# main.net
KiCad netlist of a schematic drawn in EAGLE
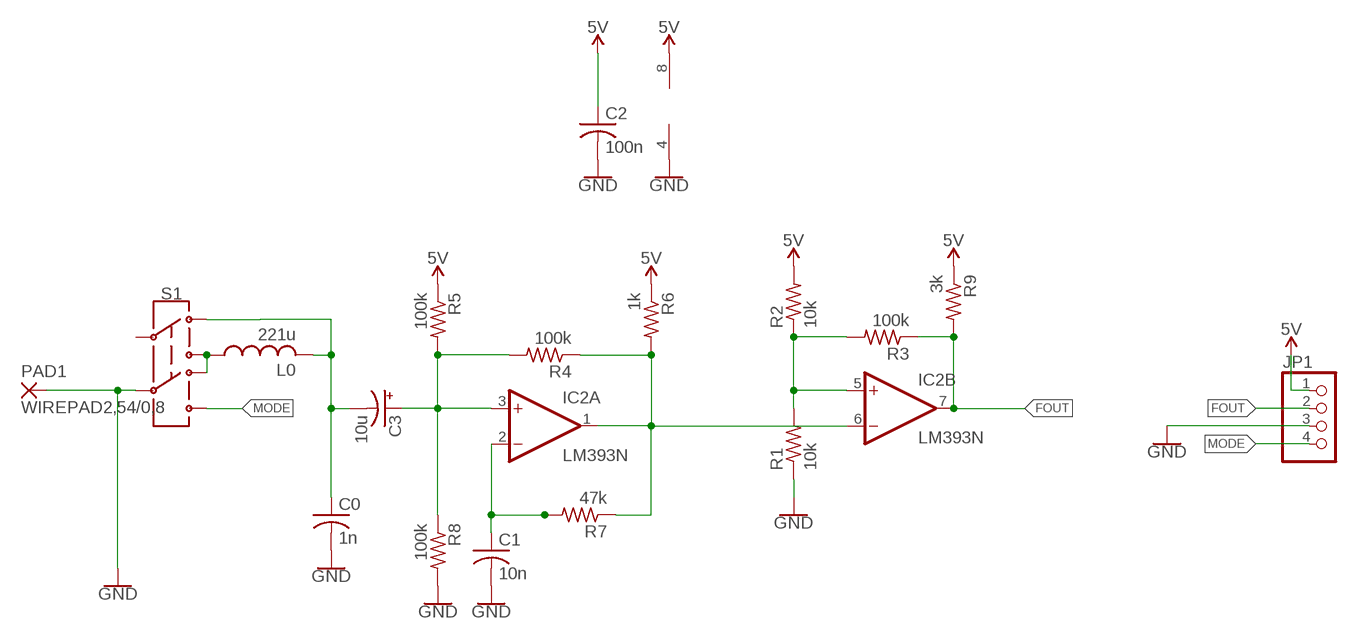
[diagram p0: schematic, sheet 1]

(export (version "E")
  (design (tool "Eeschema 10.0.6"))
  (components
    (comp (ref "C0")
      (value "1n")
      (footprint "eagle-import:C025-025X050")
      (libsource (lib "eagle-import") (part "C-US025-025X050"))
    )
    (comp (ref "C1")
      (value "10n")
      (footprint "eagle-import:C025-025X050")
      (libsource (lib "eagle-import") (part "C-US025-025X050"))
    )
    (comp (ref "C2")
      (value "100n")
      (footprint "eagle-import:C025-025X050")
      (libsource (lib "eagle-import") (part "C-US025-025X050"))
    )
    (comp (ref "C3")
      (value "10u")
      (footprint "eagle-import:E2,5-6")
      (libsource (lib "eagle-import") (part "CPOL-USE2.5-6"))
    )
    (comp (ref "IC2")
      (value "LM393N")
      (footprint "eagle-import:DIL08")
      (libsource (lib "eagle-import") (part "LM393N"))
    )
    (comp (ref "JP1")
      (value "PINHD-1X4")
      (footprint "eagle-import:1X04")
      (libsource (lib "eagle-import") (part "PINHD-1X4"))
    )
    (comp (ref "L0")
      (value "221u")
      (footprint "eagle-import:0204_5")
      (libsource (lib "eagle-import") (part "L-US0204/5"))
    )
    (comp (ref "PAD1")
      (value "WIREPAD2,54/0,8")
      (footprint "eagle-import:2,54_0,8")
      (libsource (lib "eagle-import") (part "WIREPAD2,54/0,8"))
    )
    (comp (ref "R1")
      (value "10k")
      (footprint "eagle-import:0204_7")
      (libsource (lib "eagle-import") (part "R-US_0204/7"))
    )
    (comp (ref "R2")
      (value "10k")
      (footprint "eagle-import:0207_10")
      (libsource (lib "eagle-import") (part "R-US_0207/10"))
    )
    (comp (ref "R3")
      (value "100k")
      (footprint "eagle-import:0207_10")
      (libsource (lib "eagle-import") (part "R-US_0207/10"))
    )
    (comp (ref "R4")
      (value "100k")
      (footprint "eagle-import:0207_10")
      (libsource (lib "eagle-import") (part "R-US_0207/10"))
    )
    (comp (ref "R5")
      (value "100k")
      (footprint "eagle-import:0207_10")
      (libsource (lib "eagle-import") (part "R-US_0207/10"))
    )
    (comp (ref "R6")
      (value "1k")
      (footprint "eagle-import:0207_10")
      (libsource (lib "eagle-import") (part "R-US_0207/10"))
    )
    (comp (ref "R7")
      (value "47k")
      (footprint "eagle-import:0207_10")
      (libsource (lib "eagle-import") (part "R-US_0207/10"))
    )
    (comp (ref "R8")
      (value "100k")
      (footprint "eagle-import:0207_10")
      (libsource (lib "eagle-import") (part "R-US_0207/10"))
    )
    (comp (ref "R9")
      (value "3k")
      (footprint "eagle-import:0207_10")
      (libsource (lib "eagle-import") (part "R-US_0207/10"))
    )
    (comp (ref "S1")
      (value "SWITCH-DPDT-PTH-GPI-152-3013")
      (footprint "eagle-import:SWITCH_DPDT_PTH_GPI-152-3013")
      (libsource (lib "eagle-import") (part "SWITCH-DPDT-PTH-GPI-152-3013"))
    )
  )
  (nets
    (net (code "1") (name "5V") (class "Default")
      (node (ref "C2") (pin "1") (pinfunction "1_1") (pintype "passive"))
      (node (ref "IC2") (pin "8") (pinfunction "V+_8") (pintype "power_in"))
      (node (ref "JP1") (pin "1") (pinfunction "1_1") (pintype "passive"))
      (node (ref "R2") (pin "2") (pinfunction "2_2") (pintype "passive"))
      (node (ref "R5") (pin "1") (pinfunction "1_1") (pintype "passive"))
      (node (ref "R6") (pin "1") (pinfunction "1_1") (pintype "passive"))
      (node (ref "R9") (pin "1") (pinfunction "1_1") (pintype "passive"))
    )
    (net (code "2") (name "FOUT") (class "Default")
      (node (ref "IC2") (pin "7") (pinfunction "OUT_7") (pintype "output"))
      (node (ref "JP1") (pin "2") (pinfunction "2_2") (pintype "passive"))
      (node (ref "R3") (pin "1") (pinfunction "1_1") (pintype "passive"))
      (node (ref "R9") (pin "2") (pinfunction "2_2") (pintype "passive"))
    )
    (net (code "3") (name "GND") (class "Default")
      (node (ref "C0") (pin "2") (pinfunction "2_2") (pintype "passive"))
      (node (ref "C1") (pin "2") (pinfunction "2_2") (pintype "passive"))
      (node (ref "C2") (pin "2") (pinfunction "2_2") (pintype "passive"))
      (node (ref "IC2") (pin "4") (pinfunction "V-_4") (pintype "power_in"))
      (node (ref "JP1") (pin "3") (pinfunction "3_3") (pintype "passive"))
      (node (ref "PAD1") (pin "1") (pinfunction "P_1") (pintype "passive"))
      (node (ref "R1") (pin "1") (pinfunction "1_1") (pintype "passive"))
      (node (ref "R8") (pin "2") (pinfunction "2_2") (pintype "passive"))
      (node (ref "S1") (pin "C@2") (pinfunction "5_C@2") (pintype "bidirectional"))
    )
    (net (code "4") (name "MODE") (class "Default")
      (node (ref "JP1") (pin "4") (pinfunction "4_4") (pintype "passive"))
      (node (ref "S1") (pin "21") (pinfunction "6_21") (pintype "bidirectional"))
    )
    (net (code "5") (name "Net-(IC2A-+IN)") (class "Default")
      (node (ref "C3") (pin "+") (pinfunction "+_+") (pintype "passive"))
      (node (ref "IC2") (pin "3") (pinfunction "+IN_3") (pintype "input"))
      (node (ref "R4") (pin "2") (pinfunction "2_2") (pintype "passive"))
      (node (ref "R5") (pin "2") (pinfunction "2_2") (pintype "passive"))
      (node (ref "R8") (pin "1") (pinfunction "1_1") (pintype "passive"))
    )
    (net (code "6") (name "Net-(IC2A--IN)") (class "Default")
      (node (ref "C1") (pin "1") (pinfunction "1_1") (pintype "passive"))
      (node (ref "IC2") (pin "2") (pinfunction "-IN_2") (pintype "input"))
      (node (ref "R7") (pin "2") (pinfunction "2_2") (pintype "passive"))
    )
    (net (code "7") (name "Net-(IC2A-OUT)") (class "Default")
      (node (ref "IC2") (pin "1") (pinfunction "OUT_1") (pintype "output"))
      (node (ref "IC2") (pin "6") (pinfunction "-IN_6") (pintype "input"))
      (node (ref "R4") (pin "1") (pinfunction "1_1") (pintype "passive"))
      (node (ref "R6") (pin "2") (pinfunction "2_2") (pintype "passive"))
      (node (ref "R7") (pin "1") (pinfunction "1_1") (pintype "passive"))
    )
    (net (code "8") (name "Net-(IC2B-+IN)") (class "Default")
      (node (ref "IC2") (pin "5") (pinfunction "+IN_5") (pintype "input"))
      (node (ref "R1") (pin "2") (pinfunction "2_2") (pintype "passive"))
      (node (ref "R2") (pin "1") (pinfunction "1_1") (pintype "passive"))
      (node (ref "R3") (pin "2") (pinfunction "2_2") (pintype "passive"))
    )
    (net (code "9") (name "Net-(S1-1)") (class "Default")
      (node (ref "C0") (pin "1") (pinfunction "1_1") (pintype "passive"))
      (node (ref "C3") (pin "-") (pinfunction "-_-") (pintype "passive"))
      (node (ref "L0") (pin "2") (pinfunction "2_2") (pintype "passive"))
      (node (ref "S1") (pin "10") (pinfunction "1_10") (pintype "bidirectional"))
    )
    (net (code "10") (name "Net-(S1-3)") (class "Default")
      (node (ref "L0") (pin "1") (pinfunction "1_1") (pintype "passive"))
      (node (ref "S1") (pin "11") (pinfunction "4_11") (pintype "bidirectional"))
      (node (ref "S1") (pin "20") (pinfunction "3_20") (pintype "bidirectional"))
    )
    (net (code "11") (name "unconnected-(S1-2-PadC@1)") (class "Default")
      (node (ref "S1") (pin "C@1") (pinfunction "2_C@1") (pintype "bidirectional"))
    )
  )
)
